# MrAdapteur.net
KiCad netlist of a schematic drawn in EAGLE
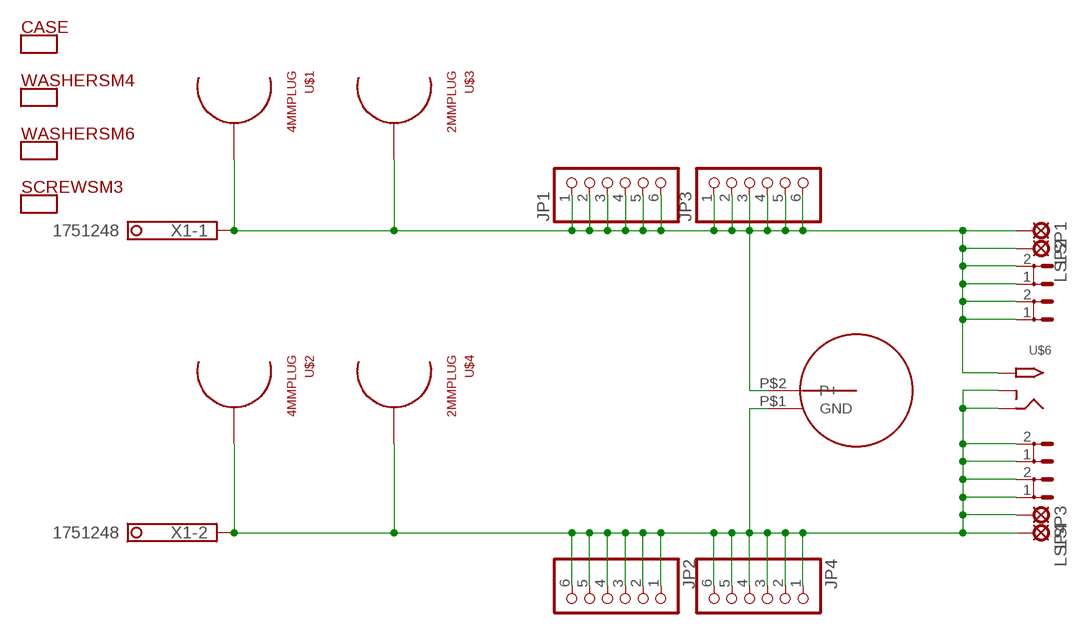
[diagram p0: schematic, sheet 1]

(export (version "E")
  (design (tool "Eeschema 10.0.6"))
  (components
    (comp (ref "JP1")
      (value "PINHD-1X6")
      (footprint "eagle-import:1X06")
      (libsource (lib "eagle-import") (part "PINHD-1X6"))
    )
    (comp (ref "JP2")
      (value "PINHD-1X6")
      (footprint "eagle-import:1X06")
      (libsource (lib "eagle-import") (part "PINHD-1X6"))
    )
    (comp (ref "JP3")
      (value "PINHD-1X6")
      (footprint "eagle-import:1X06")
      (libsource (lib "eagle-import") (part "PINHD-1X6"))
    )
    (comp (ref "JP4")
      (value "PINHD-1X6")
      (footprint "eagle-import:1X06")
      (libsource (lib "eagle-import") (part "PINHD-1X6"))
    )
    (comp (ref "LSP1")
      (value "LSP11")
      (footprint "eagle-import:LSP11")
      (libsource (lib "eagle-import") (part "LSP11"))
    )
    (comp (ref "LSP2")
      (value "LSP11")
      (footprint "eagle-import:LSP11")
      (libsource (lib "eagle-import") (part "LSP11"))
    )
    (comp (ref "LSP3")
      (value "LSP11")
      (footprint "eagle-import:LSP11")
      (libsource (lib "eagle-import") (part "LSP11"))
    )
    (comp (ref "LSP4")
      (value "LSP11")
      (footprint "eagle-import:LSP11")
      (libsource (lib "eagle-import") (part "LSP11"))
    )
    (comp (ref "U$1")
      (value "4MMPLUG")
      (footprint "eagle-import:4MMPLUG")
      (libsource (lib "eagle-import") (part "4MMPLUG"))
    )
    (comp (ref "U$2")
      (value "4MMPLUG")
      (footprint "eagle-import:4MMPLUG")
      (libsource (lib "eagle-import") (part "4MMPLUG"))
    )
    (comp (ref "U$3")
      (value "2MMPLUG")
      (footprint "eagle-import:2MMPLUG")
      (libsource (lib "eagle-import") (part "2MMPLUG"))
    )
    (comp (ref "U$4")
      (value "2MMPLUG")
      (footprint "eagle-import:2MMPLUG")
      (libsource (lib "eagle-import") (part "2MMPLUG"))
    )
    (comp (ref "U$5")
      (value "BNC")
      (footprint "eagle-import:BNC")
      (libsource (lib "eagle-import") (part "BNC"))
    )
    (comp (ref "U$6")
      (value "2.1MMJACKTHM")
      (footprint "eagle-import:PJ-102A")
      (libsource (lib "eagle-import") (part "2.1MMJACKTHM"))
    )
    (comp (ref "X1")
      (value "1751248")
      (footprint "eagle-import:1751248")
      (fields (field (name "OC_TME") "TB-3.5-P-2P/BL") (field (name "PRICE_10") "0.155"))
      (libsource (lib "eagle-import") (part "1751248"))
    )
    (comp (ref "X3")
      (value "ST4,8")
      (footprint "eagle-import:ST4,8")
      (libsource (lib "eagle-import") (part "ST4,8"))
    )
    (comp (ref "X4")
      (value "ST4,8")
      (footprint "eagle-import:ST4,8")
      (libsource (lib "eagle-import") (part "ST4,8"))
    )
    (comp (ref "X5")
      (value "ST4,8")
      (footprint "eagle-import:ST4,8")
      (libsource (lib "eagle-import") (part "ST4,8"))
    )
    (comp (ref "X6")
      (value "ST4,8")
      (footprint "eagle-import:ST4,8")
      (libsource (lib "eagle-import") (part "ST4,8"))
    )
  )
  (nets
    (net (code "1") (name "Net-(U$5-GND)") (class "Default")
      (node (ref "JP2") (pin "1") (pinfunction "1_1") (pintype "passive"))
      (node (ref "JP2") (pin "2") (pinfunction "2_2") (pintype "passive"))
      (node (ref "JP2") (pin "3") (pinfunction "3_3") (pintype "passive"))
      (node (ref "JP2") (pin "4") (pinfunction "4_4") (pintype "passive"))
      (node (ref "JP2") (pin "5") (pinfunction "5_5") (pintype "passive"))
      (node (ref "JP2") (pin "6") (pinfunction "6_6") (pintype "passive"))
      (node (ref "JP4") (pin "1") (pinfunction "1_1") (pintype "passive"))
      (node (ref "JP4") (pin "2") (pinfunction "2_2") (pintype "passive"))
      (node (ref "JP4") (pin "3") (pinfunction "3_3") (pintype "passive"))
      (node (ref "JP4") (pin "4") (pinfunction "4_4") (pintype "passive"))
      (node (ref "JP4") (pin "5") (pinfunction "5_5") (pintype "passive"))
      (node (ref "JP4") (pin "6") (pinfunction "6_6") (pintype "passive"))
      (node (ref "LSP3") (pin "MP") (pinfunction "MP_MP") (pintype "passive"))
      (node (ref "LSP4") (pin "MP") (pinfunction "MP_MP") (pintype "passive"))
      (node (ref "U$2") (pin "P$1") (pinfunction "P$1_P$1") (pintype "bidirectional"))
      (node (ref "U$4") (pin "P$1") (pinfunction "P$1_P$1") (pintype "bidirectional"))
      (node (ref "U$5") (pin "P$1") (pinfunction "GND_P$1") (pintype "bidirectional"))
      (node (ref "U$6") (pin "RING") (pinfunction "RING_RING") (pintype "bidirectional"))
      (node (ref "U$6") (pin "RING_SW") (pinfunction "RING_SW_RING_SW") (pintype "bidirectional"))
      (node (ref "X1") (pin "2") (pinfunction "K_2") (pintype "passive"))
      (node (ref "X4") (pin "1") (pinfunction "1_1") (pintype "passive"))
      (node (ref "X4") (pin "2") (pinfunction "2_2") (pintype "passive"))
      (node (ref "X6") (pin "1") (pinfunction "1_1") (pintype "passive"))
      (node (ref "X6") (pin "2") (pinfunction "2_2") (pintype "passive"))
    )
    (net (code "2") (name "Net-(U$5-P+)") (class "Default")
      (node (ref "JP1") (pin "1") (pinfunction "1_1") (pintype "passive"))
      (node (ref "JP1") (pin "2") (pinfunction "2_2") (pintype "passive"))
      (node (ref "JP1") (pin "3") (pinfunction "3_3") (pintype "passive"))
      (node (ref "JP1") (pin "4") (pinfunction "4_4") (pintype "passive"))
      (node (ref "JP1") (pin "5") (pinfunction "5_5") (pintype "passive"))
      (node (ref "JP1") (pin "6") (pinfunction "6_6") (pintype "passive"))
      (node (ref "JP3") (pin "1") (pinfunction "1_1") (pintype "passive"))
      (node (ref "JP3") (pin "2") (pinfunction "2_2") (pintype "passive"))
      (node (ref "JP3") (pin "3") (pinfunction "3_3") (pintype "passive"))
      (node (ref "JP3") (pin "4") (pinfunction "4_4") (pintype "passive"))
      (node (ref "JP3") (pin "5") (pinfunction "5_5") (pintype "passive"))
      (node (ref "JP3") (pin "6") (pinfunction "6_6") (pintype "passive"))
      (node (ref "LSP1") (pin "MP") (pinfunction "MP_MP") (pintype "passive"))
      (node (ref "LSP2") (pin "MP") (pinfunction "MP_MP") (pintype "passive"))
      (node (ref "U$1") (pin "P$1") (pinfunction "P$1_P$1") (pintype "bidirectional"))
      (node (ref "U$3") (pin "P$1") (pinfunction "P$1_P$1") (pintype "bidirectional"))
      (node (ref "U$5") (pin "P$2") (pinfunction "P+_P$2") (pintype "bidirectional"))
      (node (ref "U$6") (pin "TIP") (pinfunction "TIP_TIP") (pintype "bidirectional"))
      (node (ref "X1") (pin "1") (pinfunction "K_1") (pintype "passive"))
      (node (ref "X3") (pin "1") (pinfunction "1_1") (pintype "passive"))
      (node (ref "X3") (pin "2") (pinfunction "2_2") (pintype "passive"))
      (node (ref "X5") (pin "1") (pinfunction "1_1") (pintype "passive"))
      (node (ref "X5") (pin "2") (pinfunction "2_2") (pintype "passive"))
    )
  )
)
